# Headers.net
KiCad netlist of a schematic drawn in Altium Designer
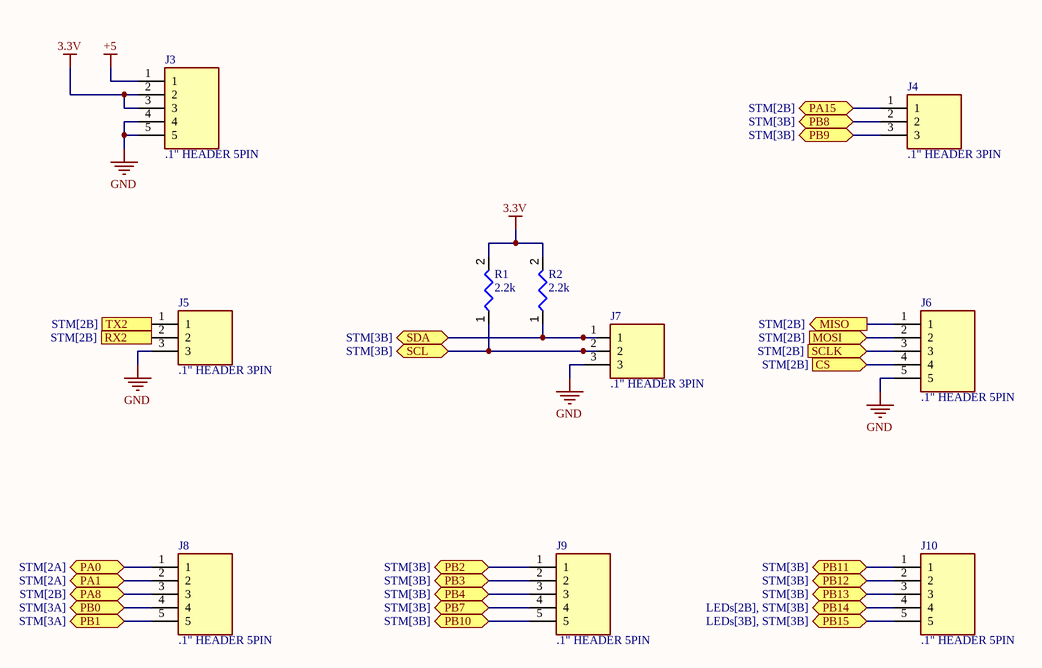
[diagram p0: Headers.SchDoc]

(export (version "E")
  (design (tool "Eeschema 10.0.6"))
  (components
    (comp (ref "J3")
      (value ".1\" HEADER 5PIN")
      (footprint "HDRV5W64P0X254_1X5_1270X250X850P")
      (description "Connector")
      (libsource (lib "Jack Bolte") (part ".1{dblquote} HEADER 5PIN"))
    )
    (comp (ref "J4")
      (value ".1\" HEADER 3PIN")
      (footprint "HDRV3W64P0X254_1X3_762X250X952P")
      (description "Connector")
      (libsource (lib "Jack Bolte") (part ".1{dblquote} HEADER 3PIN"))
    )
    (comp (ref "J5")
      (value ".1\" HEADER 3PIN")
      (footprint "HDRV3W64P0X254_1X3_762X250X952P")
      (description "Connector")
      (libsource (lib "Jack Bolte") (part ".1{dblquote} HEADER 3PIN"))
    )
    (comp (ref "J6")
      (value ".1\" HEADER 5PIN")
      (footprint "HDRV5W64P0X254_1X5_1270X250X850P")
      (description "Connector")
      (libsource (lib "Jack Bolte") (part ".1{dblquote} HEADER 5PIN"))
    )
    (comp (ref "J7")
      (value ".1\" HEADER 3PIN")
      (footprint "HDRV3W64P0X254_1X3_762X250X952P")
      (description "Connector")
      (libsource (lib "Jack Bolte") (part ".1{dblquote} HEADER 3PIN"))
    )
    (comp (ref "J8")
      (value ".1\" HEADER 5PIN")
      (footprint "HDRV5W64P0X254_1X5_1270X250X850P")
      (description "Connector")
      (libsource (lib "Jack Bolte") (part ".1{dblquote} HEADER 5PIN"))
    )
    (comp (ref "J9")
      (value ".1\" HEADER 5PIN")
      (footprint "HDRV5W64P0X254_1X5_1270X250X850P")
      (description "Connector")
      (libsource (lib "Jack Bolte") (part ".1{dblquote} HEADER 5PIN"))
    )
    (comp (ref "J10")
      (value ".1\" HEADER 5PIN")
      (footprint "HDRV5W64P0X254_1X5_1270X250X850P")
      (description "Connector")
      (libsource (lib "Jack Bolte") (part ".1{dblquote} HEADER 5PIN"))
    )
    (comp (ref "R1")
      (value "2.2k")
      (footprint "RES_0603")
      (description "Resistor 2.2k 5% 100 mW 0603")
      (fields (field (name "POWER") "100mW") (field (name "TOLERANCE") "5%"))
      (libsource (lib "Jack Bolte") (part "[0402] RES 3.3k"))
    )
    (comp (ref "R2")
      (value "2.2k")
      (footprint "RES_0603")
      (description "Resistor 2.2k 5% 100 mW 0603")
      (fields (field (name "POWER") "100mW") (field (name "TOLERANCE") "5%"))
      (libsource (lib "Jack Bolte") (part "[0402] RES 3.3k"))
    )
  )
  (nets
    (net (code "1") (name "+5") (class "Default")
      (node (ref "J3") (pin "1") (pinfunction "1_1") (pintype "passive"))
    )
    (net (code "2") (name "/CS") (class "Default")
      (node (ref "J6") (pin "4") (pinfunction "4_4") (pintype "passive"))
    )
    (net (code "3") (name "/MISO") (class "Default")
      (node (ref "J6") (pin "1") (pinfunction "1_1") (pintype "passive"))
    )
    (net (code "4") (name "/MOSI") (class "Default")
      (node (ref "J6") (pin "2") (pinfunction "2_2") (pintype "passive"))
    )
    (net (code "5") (name "/PA0") (class "Default")
      (node (ref "J8") (pin "1") (pinfunction "1_1") (pintype "passive"))
    )
    (net (code "6") (name "/PA1") (class "Default")
      (node (ref "J8") (pin "2") (pinfunction "2_2") (pintype "passive"))
    )
    (net (code "7") (name "/PA8") (class "Default")
      (node (ref "J8") (pin "3") (pinfunction "3_3") (pintype "passive"))
    )
    (net (code "8") (name "/PA15") (class "Default")
      (node (ref "J4") (pin "1") (pinfunction "1_1") (pintype "passive"))
    )
    (net (code "9") (name "/PB0") (class "Default")
      (node (ref "J8") (pin "4") (pinfunction "4_4") (pintype "passive"))
    )
    (net (code "10") (name "/PB1") (class "Default")
      (node (ref "J8") (pin "5") (pinfunction "5_5") (pintype "passive"))
    )
    (net (code "11") (name "/PB2") (class "Default")
      (node (ref "J9") (pin "1") (pinfunction "1_1") (pintype "passive"))
    )
    (net (code "12") (name "/PB3") (class "Default")
      (node (ref "J9") (pin "2") (pinfunction "2_2") (pintype "passive"))
    )
    (net (code "13") (name "/PB4") (class "Default")
      (node (ref "J9") (pin "3") (pinfunction "3_3") (pintype "passive"))
    )
    (net (code "14") (name "/PB7") (class "Default")
      (node (ref "J9") (pin "4") (pinfunction "4_4") (pintype "passive"))
    )
    (net (code "15") (name "/PB8") (class "Default")
      (node (ref "J4") (pin "2") (pinfunction "2_2") (pintype "passive"))
    )
    (net (code "16") (name "/PB9") (class "Default")
      (node (ref "J4") (pin "3") (pinfunction "3_3") (pintype "passive"))
    )
    (net (code "17") (name "/PB10") (class "Default")
      (node (ref "J9") (pin "5") (pinfunction "5_5") (pintype "passive"))
    )
    (net (code "18") (name "/PB11") (class "Default")
      (node (ref "J10") (pin "1") (pinfunction "1_1") (pintype "passive"))
    )
    (net (code "19") (name "/PB12") (class "Default")
      (node (ref "J10") (pin "2") (pinfunction "2_2") (pintype "passive"))
    )
    (net (code "20") (name "/PB13") (class "Default")
      (node (ref "J10") (pin "3") (pinfunction "3_3") (pintype "passive"))
    )
    (net (code "21") (name "/PB14") (class "Default")
      (node (ref "J10") (pin "4") (pinfunction "4_4") (pintype "passive"))
    )
    (net (code "22") (name "/PB15") (class "Default")
      (node (ref "J10") (pin "5") (pinfunction "5_5") (pintype "passive"))
    )
    (net (code "23") (name "/RX2") (class "Default")
      (node (ref "J5") (pin "2") (pinfunction "2_2") (pintype "passive"))
    )
    (net (code "24") (name "/SCL") (class "Default")
      (node (ref "J7") (pin "2") (pinfunction "2_2") (pintype "passive"))
      (node (ref "R1") (pin "1") (pinfunction "1_1") (pintype "passive"))
    )
    (net (code "25") (name "/SCLK") (class "Default")
      (node (ref "J6") (pin "3") (pinfunction "3_3") (pintype "passive"))
    )
    (net (code "26") (name "/SDA") (class "Default")
      (node (ref "J7") (pin "1") (pinfunction "1_1") (pintype "passive"))
      (node (ref "R2") (pin "1") (pinfunction "1_1") (pintype "passive"))
    )
    (net (code "27") (name "/TX2") (class "Default")
      (node (ref "J5") (pin "1") (pinfunction "1_1") (pintype "passive"))
    )
    (net (code "28") (name "3.3V") (class "Default")
      (node (ref "J3") (pin "2") (pinfunction "2_2") (pintype "passive"))
      (node (ref "J3") (pin "3") (pinfunction "3_3") (pintype "passive"))
      (node (ref "R1") (pin "2") (pinfunction "2_2") (pintype "passive"))
      (node (ref "R2") (pin "2") (pinfunction "2_2") (pintype "passive"))
    )
    (net (code "29") (name "GND") (class "Default")
      (node (ref "J3") (pin "4") (pinfunction "4_4") (pintype "passive"))
      (node (ref "J3") (pin "5") (pinfunction "5_5") (pintype "passive"))
      (node (ref "J5") (pin "3") (pinfunction "3_3") (pintype "passive"))
      (node (ref "J6") (pin "5") (pinfunction "5_5") (pintype "passive"))
      (node (ref "J7") (pin "3") (pinfunction "3_3") (pintype "passive"))
    )
  )
)
